# RobotCtrl_Core.net
KiCad netlist of a schematic drawn in Altium Designer
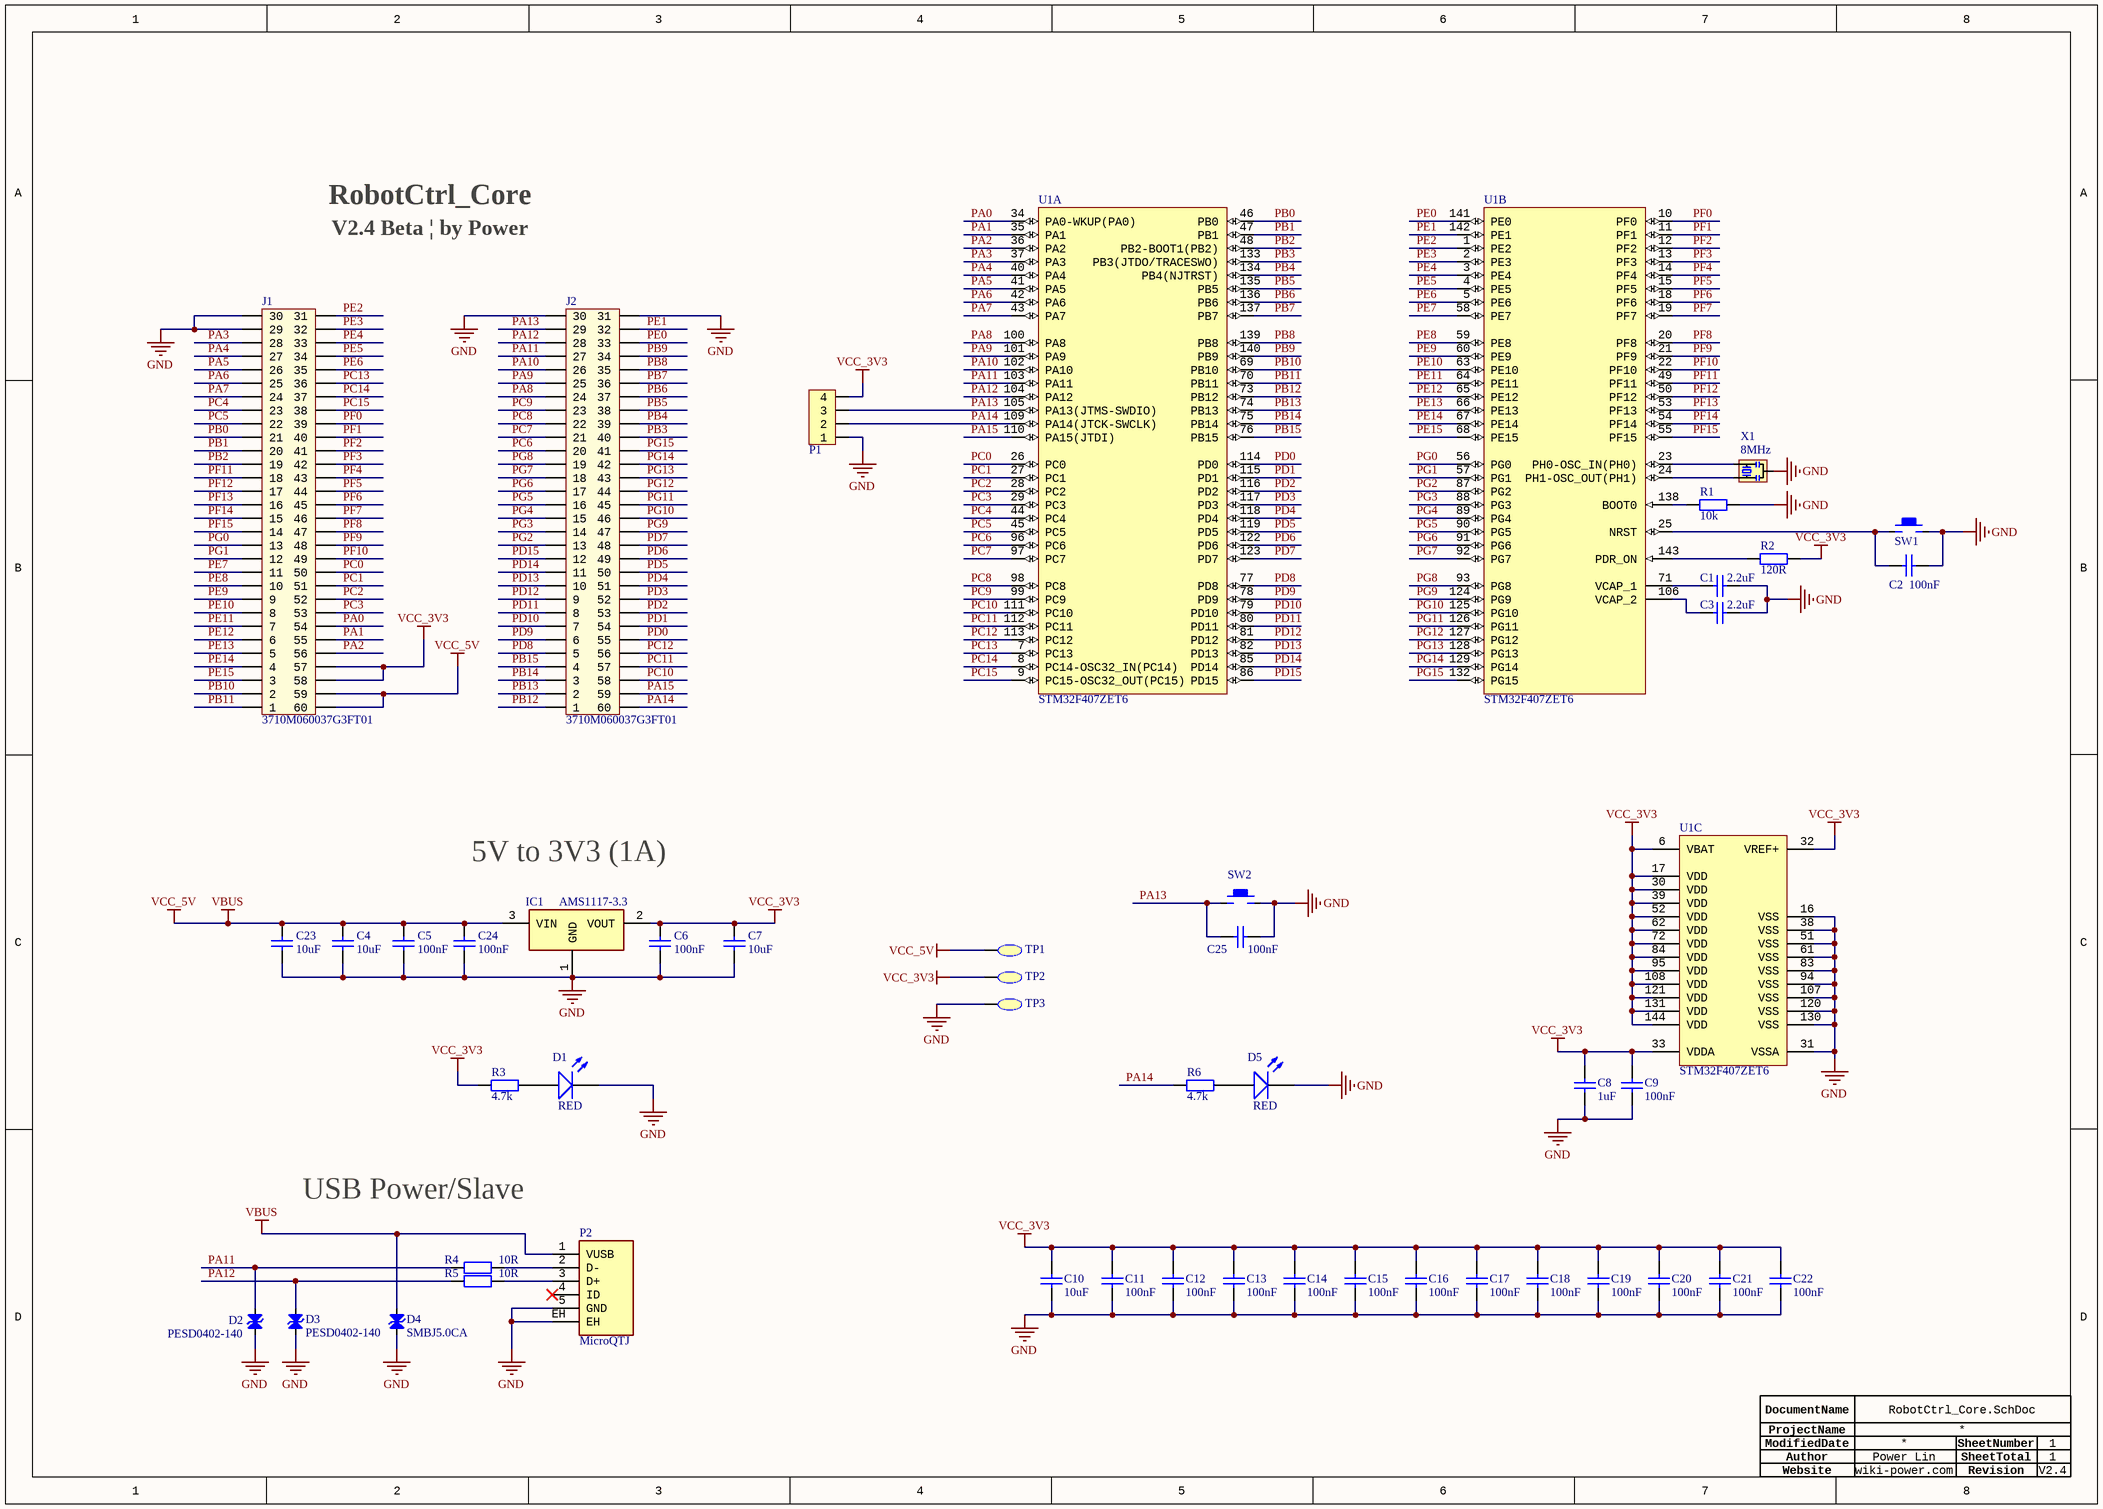
[diagram p0: RobotCtrl_Core.SchDoc]

(export (version "E")
  (design (tool "Eeschema 10.0.6"))
  (components
    (comp (ref "C1")
      (value "2.2uF")
      (footprint "CAP-0603")
      (description "贴片电容")
      (libsource (lib "Power_Lib_Altium") (part "CAP"))
    )
    (comp (ref "C2")
      (value "100nF")
      (footprint "CAP-0603")
      (description "贴片电容")
      (libsource (lib "Power_Lib_Altium") (part "CAP"))
    )
    (comp (ref "C3")
      (value "2.2uF")
      (footprint "CAP-0603")
      (description "贴片电容")
      (libsource (lib "Power_Lib_Altium") (part "CAP"))
    )
    (comp (ref "C4")
      (value "10uF")
      (footprint "CAP-0603")
      (description "贴片电容")
      (libsource (lib "Power_Lib_Altium") (part "CAP"))
    )
    (comp (ref "C5")
      (value "100nF")
      (footprint "CAP-0603")
      (description "贴片电容")
      (libsource (lib "Power_Lib_Altium") (part "CAP"))
    )
    (comp (ref "C6")
      (value "100nF")
      (footprint "CAP-0603")
      (description "贴片电容")
      (libsource (lib "Power_Lib_Altium") (part "CAP"))
    )
    (comp (ref "C7")
      (value "10uF")
      (footprint "CAP-0603")
      (description "贴片电容")
      (libsource (lib "Power_Lib_Altium") (part "CAP"))
    )
    (comp (ref "C8")
      (value "1uF")
      (footprint "CAP-0402")
      (description "贴片电容")
      (libsource (lib "Power_Lib_Altium") (part "CAP"))
    )
    (comp (ref "C9")
      (value "100nF")
      (footprint "CAP-0402")
      (description "贴片电容")
      (libsource (lib "Power_Lib_Altium") (part "CAP"))
    )
    (comp (ref "C10")
      (value "10uF")
      (footprint "CAP-0402")
      (description "贴片电容")
      (libsource (lib "Power_Lib_Altium") (part "CAP"))
    )
    (comp (ref "C11")
      (value "100nF")
      (footprint "CAP-0402")
      (description "贴片电容")
      (libsource (lib "Power_Lib_Altium") (part "CAP"))
    )
    (comp (ref "C12")
      (value "100nF")
      (footprint "CAP-0402")
      (description "贴片电容")
      (libsource (lib "Power_Lib_Altium") (part "CAP"))
    )
    (comp (ref "C13")
      (value "100nF")
      (footprint "CAP-0402")
      (description "贴片电容")
      (libsource (lib "Power_Lib_Altium") (part "CAP"))
    )
    (comp (ref "C14")
      (value "100nF")
      (footprint "CAP-0402")
      (description "贴片电容")
      (libsource (lib "Power_Lib_Altium") (part "CAP"))
    )
    (comp (ref "C15")
      (value "100nF")
      (footprint "CAP-0402")
      (description "贴片电容")
      (libsource (lib "Power_Lib_Altium") (part "CAP"))
    )
    (comp (ref "C16")
      (value "100nF")
      (footprint "CAP-0402")
      (description "贴片电容")
      (libsource (lib "Power_Lib_Altium") (part "CAP"))
    )
    (comp (ref "C17")
      (value "100nF")
      (footprint "CAP-0402")
      (description "贴片电容")
      (libsource (lib "Power_Lib_Altium") (part "CAP"))
    )
    (comp (ref "C18")
      (value "100nF")
      (footprint "CAP-0402")
      (description "贴片电容")
      (libsource (lib "Power_Lib_Altium") (part "CAP"))
    )
    (comp (ref "C19")
      (value "100nF")
      (footprint "CAP-0402")
      (description "贴片电容")
      (libsource (lib "Power_Lib_Altium") (part "CAP"))
    )
    (comp (ref "C20")
      (value "100nF")
      (footprint "CAP-0402")
      (description "贴片电容")
      (libsource (lib "Power_Lib_Altium") (part "CAP"))
    )
    (comp (ref "C21")
      (value "100nF")
      (footprint "CAP-0402")
      (description "贴片电容")
      (libsource (lib "Power_Lib_Altium") (part "CAP"))
    )
    (comp (ref "C22")
      (value "100nF")
      (footprint "CAP-0402")
      (description "贴片电容")
      (libsource (lib "Power_Lib_Altium") (part "CAP"))
    )
    (comp (ref "C23")
      (value "10uF")
      (footprint "CAP-0603")
      (description "贴片电容")
      (libsource (lib "Power_Lib_Altium") (part "CAP"))
    )
    (comp (ref "C24")
      (value "100nF")
      (footprint "CAP-0603")
      (description "贴片电容")
      (libsource (lib "Power_Lib_Altium") (part "CAP"))
    )
    (comp (ref "C25")
      (value "100nF")
      (footprint "CAP-0603")
      (description "贴片电容")
      (libsource (lib "Power_Lib_Altium") (part "CAP"))
    )
    (comp (ref "D1")
      (value "RED")
      (footprint "LED-0603")
      (description "发光二极管")
      (libsource (lib "Power_Lib_Altium") (part "LED"))
    )
    (comp (ref "D2")
      (value "PESD0402-140")
      (footprint "D-0402")
      (libsource (lib "Power_Lib_Altium") (part "TVS_C"))
    )
    (comp (ref "D3")
      (value "PESD0402-140")
      (footprint "D-0402")
      (libsource (lib "Power_Lib_Altium") (part "TVS_C"))
    )
    (comp (ref "D4")
      (value "SMBJ5.0CA")
      (footprint "DO-214AA/SMB")
      (description "Brightking / MDD")
      (libsource (lib "Power_Lib_Altium") (part "TVS_C"))
    )
    (comp (ref "D5")
      (value "RED")
      (footprint "LED-0603")
      (description "发光二极管")
      (libsource (lib "Power_Lib_Altium") (part "LED"))
    )
    (comp (ref "IC1")
      (value "AMS1117-3.3")
      (footprint "SOT-223")
      (description "AMS1117-3.3 1.0A")
      (fields (field (name "MANUFACTURER_PART_NUMBER") "SI2302DS") (field (name "RS PART NUMBER") "7983053P"))
      (libsource (lib "Power_Lib_Altium") (part "AMS1117"))
    )
    (comp (ref "J1")
      (value "3710M060037G3FT01")
      (footprint "3710M060037G3FT01")
      (description "B2B Connector")
      (libsource (lib "Power_Lib_Altium") (part "3710M/F"))
    )
    (comp (ref "J2")
      (value "3710M060037G3FT01")
      (footprint "3710M060037G3FT01")
      (description "B2B Connector")
      (libsource (lib "Power_Lib_Altium") (part "3710M/F"))
    )
    (comp (ref "P1")
      (value "HDR1x4_2.54")
      (footprint "HDR1X4_2.54")
      (description "Header")
      (libsource (lib "Power_Lib_Altium") (part "HDR1x4_2.54"))
    )
    (comp (ref "P2")
      (value "MicroQTJ")
      (footprint "USB-MICRO")
      (description "USB_MICRO")
      (libsource (lib "Power_Lib_Altium") (part "USB_MICRO"))
    )
    (comp (ref "R1")
      (value "10k")
      (footprint "R-0603")
      (description "贴片电阻")
      (libsource (lib "") (part "RES_1"))
    )
    (comp (ref "R2")
      (value "120R")
      (footprint "R-0603")
      (description "贴片电阻")
      (libsource (lib "") (part "RES_1"))
    )
    (comp (ref "R3")
      (value "4.7k")
      (footprint "R-0603")
      (description "贴片电阻")
      (libsource (lib "") (part "RES_1"))
    )
    (comp (ref "R4")
      (value "10R")
      (footprint "R-0603")
      (description "贴片电阻")
      (libsource (lib "Power_Lib_Altium") (part "RES"))
    )
    (comp (ref "R5")
      (value "10R")
      (footprint "R-0603")
      (description "贴片电阻")
      (libsource (lib "Power_Lib_Altium") (part "RES"))
    )
    (comp (ref "R6")
      (value "4.7k")
      (footprint "R-0603")
      (description "贴片电阻")
      (libsource (lib "") (part "RES_1"))
    )
    (comp (ref "SW1")
      (value "KEY")
      (footprint "KEY-4P-4.2*3.4*2.5")
      (description "按键开关")
      (libsource (lib "Power_Lib_Altium") (part "KEY"))
    )
    (comp (ref "SW2")
      (value "KEY")
      (footprint "KEY-4P-4.2*3.4*2.5")
      (description "按键开关")
      (libsource (lib "Power_Lib_Altium") (part "KEY"))
    )
    (comp (ref "TP1")
      (value "TestPoint")
      (footprint "TestPoint")
      (description "测试点")
      (libsource (lib "Power_Lib_Altium") (part "TestPoint"))
    )
    (comp (ref "TP2")
      (value "TestPoint")
      (footprint "TestPoint")
      (description "测试点")
      (libsource (lib "Power_Lib_Altium") (part "TestPoint"))
    )
    (comp (ref "TP3")
      (value "TestPoint")
      (footprint "TestPoint")
      (description "测试点")
      (libsource (lib "Power_Lib_Altium") (part "TestPoint"))
    )
    (comp (ref "U1")
      (value "STM32F407ZET6")
      (footprint "STM-LQFP144_N")
      (fields (field (name "MANUFACTURER") "STMicroelectronics"))
      (libsource (lib "Power_Lib_Altium") (part "STM32F407ZET6"))
    )
    (comp (ref "X1")
      (value "8MHz")
      (footprint "SMD3213-3P")
      (description "CSTCE8M00G15C99-R0")
      (libsource (lib "Power_Lib_Altium") (part "XTAL"))
    )
  )
  (nets
    (net (code "1") (name "/PA0") (class "Default")
      (node (ref "J1") (pin "54") (pinfunction "54_54") (pintype "passive"))
      (node (ref "U1") (pin "34") (pinfunction "PA0-WKUP(PA0)_34") (pintype "bidirectional"))
    )
    (net (code "2") (name "/PA1") (class "Default")
      (node (ref "J1") (pin "55") (pinfunction "55_55") (pintype "passive"))
      (node (ref "U1") (pin "35") (pinfunction "PA1_35") (pintype "bidirectional"))
    )
    (net (code "3") (name "/PA2") (class "Default")
      (node (ref "J1") (pin "56") (pinfunction "56_56") (pintype "passive"))
      (node (ref "U1") (pin "36") (pinfunction "PA2_36") (pintype "bidirectional"))
    )
    (net (code "4") (name "/PA3") (class "Default")
      (node (ref "J1") (pin "28") (pinfunction "28_28") (pintype "passive"))
      (node (ref "U1") (pin "37") (pinfunction "PA3_37") (pintype "bidirectional"))
    )
    (net (code "5") (name "/PA4") (class "Default")
      (node (ref "J1") (pin "27") (pinfunction "27_27") (pintype "passive"))
      (node (ref "U1") (pin "40") (pinfunction "PA4_40") (pintype "bidirectional"))
    )
    (net (code "6") (name "/PA5") (class "Default")
      (node (ref "J1") (pin "26") (pinfunction "26_26") (pintype "passive"))
      (node (ref "U1") (pin "41") (pinfunction "PA5_41") (pintype "bidirectional"))
    )
    (net (code "7") (name "/PA6") (class "Default")
      (node (ref "J1") (pin "25") (pinfunction "25_25") (pintype "passive"))
      (node (ref "U1") (pin "42") (pinfunction "PA6_42") (pintype "bidirectional"))
    )
    (net (code "8") (name "/PA7") (class "Default")
      (node (ref "J1") (pin "24") (pinfunction "24_24") (pintype "passive"))
      (node (ref "U1") (pin "43") (pinfunction "PA7_43") (pintype "bidirectional"))
    )
    (net (code "9") (name "/PA8") (class "Default")
      (node (ref "J2") (pin "24") (pinfunction "24_24") (pintype "passive"))
      (node (ref "U1") (pin "100") (pinfunction "PA8_100") (pintype "bidirectional"))
    )
    (net (code "10") (name "/PA9") (class "Default")
      (node (ref "J2") (pin "25") (pinfunction "25_25") (pintype "passive"))
      (node (ref "U1") (pin "101") (pinfunction "PA9_101") (pintype "bidirectional"))
    )
    (net (code "11") (name "/PA10") (class "Default")
      (node (ref "J2") (pin "26") (pinfunction "26_26") (pintype "passive"))
      (node (ref "U1") (pin "102") (pinfunction "PA10_102") (pintype "bidirectional"))
    )
    (net (code "12") (name "/PA11") (class "Default")
      (node (ref "D2") (pin "2") (pinfunction "2_2") (pintype "passive"))
      (node (ref "J2") (pin "27") (pinfunction "27_27") (pintype "passive"))
      (node (ref "R4") (pin "1") (pinfunction "1_1") (pintype "passive"))
      (node (ref "U1") (pin "103") (pinfunction "PA11_103") (pintype "bidirectional"))
    )
    (net (code "13") (name "/PA12") (class "Default")
      (node (ref "D3") (pin "2") (pinfunction "2_2") (pintype "passive"))
      (node (ref "J2") (pin "28") (pinfunction "28_28") (pintype "passive"))
      (node (ref "R5") (pin "1") (pinfunction "1_1") (pintype "passive"))
      (node (ref "U1") (pin "104") (pinfunction "PA12_104") (pintype "bidirectional"))
    )
    (net (code "14") (name "/PA13") (class "Default")
      (node (ref "C25") (pin "2") (pinfunction "2_2") (pintype "passive"))
      (node (ref "J2") (pin "29") (pinfunction "29_29") (pintype "passive"))
      (node (ref "P1") (pin "3") (pinfunction "3_3") (pintype "passive"))
      (node (ref "SW2") (pin "1") (pinfunction "1_1") (pintype "passive"))
      (node (ref "U1") (pin "105") (pinfunction "PA13(JTMS-SWDIO)_105") (pintype "bidirectional"))
    )
    (net (code "15") (name "/PA14") (class "Default")
      (node (ref "J2") (pin "60") (pinfunction "60_60") (pintype "passive"))
      (node (ref "P1") (pin "2") (pinfunction "2_2") (pintype "passive"))
      (node (ref "R6") (pin "2") (pinfunction "2_2") (pintype "passive"))
      (node (ref "U1") (pin "109") (pinfunction "PA14(JTCK-SWCLK)_109") (pintype "bidirectional"))
    )
    (net (code "16") (name "/PA15") (class "Default")
      (node (ref "J2") (pin "59") (pinfunction "59_59") (pintype "passive"))
      (node (ref "U1") (pin "110") (pinfunction "PA15(JTDI)_110") (pintype "bidirectional"))
    )
    (net (code "17") (name "/PB0") (class "Default")
      (node (ref "J1") (pin "21") (pinfunction "21_21") (pintype "passive"))
      (node (ref "U1") (pin "46") (pinfunction "PB0_46") (pintype "bidirectional"))
    )
    (net (code "18") (name "/PB1") (class "Default")
      (node (ref "J1") (pin "20") (pinfunction "20_20") (pintype "passive"))
      (node (ref "U1") (pin "47") (pinfunction "PB1_47") (pintype "bidirectional"))
    )
    (net (code "19") (name "/PB2") (class "Default")
      (node (ref "J1") (pin "19") (pinfunction "19_19") (pintype "passive"))
      (node (ref "U1") (pin "48") (pinfunction "PB2-BOOT1(PB2)_48") (pintype "bidirectional"))
    )
    (net (code "20") (name "/PB3") (class "Default")
      (node (ref "J2") (pin "40") (pinfunction "40_40") (pintype "passive"))
      (node (ref "U1") (pin "133") (pinfunction "PB3(JTDO/TRACESWO)_133") (pintype "bidirectional"))
    )
    (net (code "21") (name "/PB4") (class "Default")
      (node (ref "J2") (pin "39") (pinfunction "39_39") (pintype "passive"))
      (node (ref "U1") (pin "134") (pinfunction "PB4(NJTRST)_134") (pintype "bidirectional"))
    )
    (net (code "22") (name "/PB5") (class "Default")
      (node (ref "J2") (pin "38") (pinfunction "38_38") (pintype "passive"))
      (node (ref "U1") (pin "135") (pinfunction "PB5_135") (pintype "bidirectional"))
    )
    (net (code "23") (name "/PB6") (class "Default")
      (node (ref "J2") (pin "37") (pinfunction "37_37") (pintype "passive"))
      (node (ref "U1") (pin "136") (pinfunction "PB6_136") (pintype "bidirectional"))
    )
    (net (code "24") (name "/PB7") (class "Default")
      (node (ref "J2") (pin "36") (pinfunction "36_36") (pintype "passive"))
      (node (ref "U1") (pin "137") (pinfunction "PB7_137") (pintype "bidirectional"))
    )
    (net (code "25") (name "/PB8") (class "Default")
      (node (ref "J2") (pin "35") (pinfunction "35_35") (pintype "passive"))
      (node (ref "U1") (pin "139") (pinfunction "PB8_139") (pintype "bidirectional"))
    )
    (net (code "26") (name "/PB9") (class "Default")
      (node (ref "J2") (pin "34") (pinfunction "34_34") (pintype "passive"))
      (node (ref "U1") (pin "140") (pinfunction "PB9_140") (pintype "bidirectional"))
    )
    (net (code "27") (name "/PB10") (class "Default")
      (node (ref "J1") (pin "2") (pinfunction "2_2") (pintype "passive"))
      (node (ref "U1") (pin "69") (pinfunction "PB10_69") (pintype "bidirectional"))
    )
    (net (code "28") (name "/PB11") (class "Default")
      (node (ref "J1") (pin "1") (pinfunction "1_1") (pintype "passive"))
      (node (ref "U1") (pin "70") (pinfunction "PB11_70") (pintype "bidirectional"))
    )
    (net (code "29") (name "/PB12") (class "Default")
      (node (ref "J2") (pin "1") (pinfunction "1_1") (pintype "passive"))
      (node (ref "U1") (pin "73") (pinfunction "PB12_73") (pintype "bidirectional"))
    )
    (net (code "30") (name "/PB13") (class "Default")
      (node (ref "J2") (pin "2") (pinfunction "2_2") (pintype "passive"))
      (node (ref "U1") (pin "74") (pinfunction "PB13_74") (pintype "bidirectional"))
    )
    (net (code "31") (name "/PB14") (class "Default")
      (node (ref "J2") (pin "3") (pinfunction "3_3") (pintype "passive"))
      (node (ref "U1") (pin "75") (pinfunction "PB14_75") (pintype "bidirectional"))
    )
    (net (code "32") (name "/PB15") (class "Default")
      (node (ref "J2") (pin "4") (pinfunction "4_4") (pintype "passive"))
      (node (ref "U1") (pin "76") (pinfunction "PB15_76") (pintype "bidirectional"))
    )
    (net (code "33") (name "/PC0") (class "Default")
      (node (ref "J1") (pin "50") (pinfunction "50_50") (pintype "passive"))
      (node (ref "U1") (pin "26") (pinfunction "PC0_26") (pintype "bidirectional"))
    )
    (net (code "34") (name "/PC1") (class "Default")
      (node (ref "J1") (pin "51") (pinfunction "51_51") (pintype "passive"))
      (node (ref "U1") (pin "27") (pinfunction "PC1_27") (pintype "bidirectional"))
    )
    (net (code "35") (name "/PC2") (class "Default")
      (node (ref "J1") (pin "52") (pinfunction "52_52") (pintype "passive"))
      (node (ref "U1") (pin "28") (pinfunction "PC2_28") (pintype "bidirectional"))
    )
    (net (code "36") (name "/PC3") (class "Default")
      (node (ref "J1") (pin "53") (pinfunction "53_53") (pintype "passive"))
      (node (ref "U1") (pin "29") (pinfunction "PC3_29") (pintype "bidirectional"))
    )
    (net (code "37") (name "/PC4") (class "Default")
      (node (ref "J1") (pin "23") (pinfunction "23_23") (pintype "passive"))
      (node (ref "U1") (pin "44") (pinfunction "PC4_44") (pintype "bidirectional"))
    )
    (net (code "38") (name "/PC5") (class "Default")
      (node (ref "J1") (pin "22") (pinfunction "22_22") (pintype "passive"))
      (node (ref "U1") (pin "45") (pinfunction "PC5_45") (pintype "bidirectional"))
    )
    (net (code "39") (name "/PC6") (class "Default")
      (node (ref "J2") (pin "20") (pinfunction "20_20") (pintype "passive"))
      (node (ref "U1") (pin "96") (pinfunction "PC6_96") (pintype "bidirectional"))
    )
    (net (code "40") (name "/PC7") (class "Default")
      (node (ref "J2") (pin "21") (pinfunction "21_21") (pintype "passive"))
      (node (ref "U1") (pin "97") (pinfunction "PC7_97") (pintype "bidirectional"))
    )
    (net (code "41") (name "/PC8") (class "Default")
      (node (ref "J2") (pin "22") (pinfunction "22_22") (pintype "passive"))
      (node (ref "U1") (pin "98") (pinfunction "PC8_98") (pintype "bidirectional"))
    )
    (net (code "42") (name "/PC9") (class "Default")
      (node (ref "J2") (pin "23") (pinfunction "23_23") (pintype "passive"))
      (node (ref "U1") (pin "99") (pinfunction "PC9_99") (pintype "bidirectional"))
    )
    (net (code "43") (name "/PC10") (class "Default")
      (node (ref "J2") (pin "58") (pinfunction "58_58") (pintype "passive"))
      (node (ref "U1") (pin "111") (pinfunction "PC10_111") (pintype "bidirectional"))
    )
    (net (code "44") (name "/PC11") (class "Default")
      (node (ref "J2") (pin "57") (pinfunction "57_57") (pintype "passive"))
      (node (ref "U1") (pin "112") (pinfunction "PC11_112") (pintype "bidirectional"))
    )
    (net (code "45") (name "/PC12") (class "Default")
      (node (ref "J2") (pin "56") (pinfunction "56_56") (pintype "passive"))
      (node (ref "U1") (pin "113") (pinfunction "PC12_113") (pintype "bidirectional"))
    )
    (net (code "46") (name "/PC13") (class "Default")
      (node (ref "J1") (pin "36") (pinfunction "36_36") (pintype "passive"))
      (node (ref "U1") (pin "7") (pinfunction "PC13_7") (pintype "bidirectional"))
    )
    (net (code "47") (name "/PC14") (class "Default")
      (node (ref "J1") (pin "37") (pinfunction "37_37") (pintype "passive"))
      (node (ref "U1") (pin "8") (pinfunction "PC14-OSC32_IN(PC14)_8") (pintype "bidirectional"))
    )
    (net (code "48") (name "/PC15") (class "Default")
      (node (ref "J1") (pin "38") (pinfunction "38_38") (pintype "passive"))
      (node (ref "U1") (pin "9") (pinfunction "PC15-OSC32_OUT(PC15)_9") (pintype "bidirectional"))
    )
    (net (code "49") (name "/PD0") (class "Default")
      (node (ref "J2") (pin "55") (pinfunction "55_55") (pintype "passive"))
      (node (ref "U1") (pin "114") (pinfunction "PD0_114") (pintype "bidirectional"))
    )
    (net (code "50") (name "/PD1") (class "Default")
      (node (ref "J2") (pin "54") (pinfunction "54_54") (pintype "passive"))
      (node (ref "U1") (pin "115") (pinfunction "PD1_115") (pintype "bidirectional"))
    )
    (net (code "51") (name "/PD2") (class "Default")
      (node (ref "J2") (pin "53") (pinfunction "53_53") (pintype "passive"))
      (node (ref "U1") (pin "116") (pinfunction "PD2_116") (pintype "bidirectional"))
    )
    (net (code "52") (name "/PD3") (class "Default")
      (node (ref "J2") (pin "52") (pinfunction "52_52") (pintype "passive"))
      (node (ref "U1") (pin "117") (pinfunction "PD3_117") (pintype "bidirectional"))
    )
    (net (code "53") (name "/PD4") (class "Default")
      (node (ref "J2") (pin "51") (pinfunction "51_51") (pintype "passive"))
      (node (ref "U1") (pin "118") (pinfunction "PD4_118") (pintype "bidirectional"))
    )
    (net (code "54") (name "/PD5") (class "Default")
      (node (ref "J2") (pin "50") (pinfunction "50_50") (pintype "passive"))
      (node (ref "U1") (pin "119") (pinfunction "PD5_119") (pintype "bidirectional"))
    )
    (net (code "55") (name "/PD6") (class "Default")
      (node (ref "J2") (pin "49") (pinfunction "49_49") (pintype "passive"))
      (node (ref "U1") (pin "122") (pinfunction "PD6_122") (pintype "bidirectional"))
    )
    (net (code "56") (name "/PD7") (class "Default")
      (node (ref "J2") (pin "48") (pinfunction "48_48") (pintype "passive"))
      (node (ref "U1") (pin "123") (pinfunction "PD7_123") (pintype "bidirectional"))
    )
    (net (code "57") (name "/PD8") (class "Default")
      (node (ref "J2") (pin "5") (pinfunction "5_5") (pintype "passive"))
      (node (ref "U1") (pin "77") (pinfunction "PD8_77") (pintype "bidirectional"))
    )
    (net (code "58") (name "/PD9") (class "Default")
      (node (ref "J2") (pin "6") (pinfunction "6_6") (pintype "passive"))
      (node (ref "U1") (pin "78") (pinfunction "PD9_78") (pintype "bidirectional"))
    )
    (net (code "59") (name "/PD10") (class "Default")
      (node (ref "J2") (pin "7") (pinfunction "7_7") (pintype "passive"))
      (node (ref "U1") (pin "79") (pinfunction "PD10_79") (pintype "bidirectional"))
    )
    (net (code "60") (name "/PD11") (class "Default")
      (node (ref "J2") (pin "8") (pinfunction "8_8") (pintype "passive"))
      (node (ref "U1") (pin "80") (pinfunction "PD11_80") (pintype "bidirectional"))
    )
    (net (code "61") (name "/PD12") (class "Default")
      (node (ref "J2") (pin "9") (pinfunction "9_9") (pintype "passive"))
      (node (ref "U1") (pin "81") (pinfunction "PD12_81") (pintype "bidirectional"))
    )
    (net (code "62") (name "/PD13") (class "Default")
      (node (ref "J2") (pin "10") (pinfunction "10_10") (pintype "passive"))
      (node (ref "U1") (pin "82") (pinfunction "PD13_82") (pintype "bidirectional"))
    )
    (net (code "63") (name "/PD14") (class "Default")
      (node (ref "J2") (pin "11") (pinfunction "11_11") (pintype "passive"))
      (node (ref "U1") (pin "85") (pinfunction "PD14_85") (pintype "bidirectional"))
    )
    (net (code "64") (name "/PD15") (class "Default")
      (node (ref "J2") (pin "12") (pinfunction "12_12") (pintype "passive"))
      (node (ref "U1") (pin "86") (pinfunction "PD15_86") (pintype "bidirectional"))
    )
    (net (code "65") (name "/PE0") (class "Default")
      (node (ref "J2") (pin "33") (pinfunction "33_33") (pintype "passive"))
      (node (ref "U1") (pin "141") (pinfunction "PE0_141") (pintype "bidirectional"))
    )
    (net (code "66") (name "/PE1") (class "Default")
      (node (ref "J2") (pin "32") (pinfunction "32_32") (pintype "passive"))
      (node (ref "U1") (pin "142") (pinfunction "PE1_142") (pintype "bidirectional"))
    )
    (net (code "67") (name "/PE2") (class "Default")
      (node (ref "J1") (pin "31") (pinfunction "31_31") (pintype "passive"))
      (node (ref "U1") (pin "1") (pinfunction "PE2_1") (pintype "bidirectional"))
    )
    (net (code "68") (name "/PE3") (class "Default")
      (node (ref "J1") (pin "32") (pinfunction "32_32") (pintype "passive"))
      (node (ref "U1") (pin "2") (pinfunction "PE3_2") (pintype "bidirectional"))
    )
    (net (code "69") (name "/PE4") (class "Default")
      (node (ref "J1") (pin "33") (pinfunction "33_33") (pintype "passive"))
      (node (ref "U1") (pin "3") (pinfunction "PE4_3") (pintype "bidirectional"))
    )
    (net (code "70") (name "/PE5") (class "Default")
      (node (ref "J1") (pin "34") (pinfunction "34_34") (pintype "passive"))
      (node (ref "U1") (pin "4") (pinfunction "PE5_4") (pintype "bidirectional"))
    )
    (net (code "71") (name "/PE6") (class "Default")
      (node (ref "J1") (pin "35") (pinfunction "35_35") (pintype "passive"))
      (node (ref "U1") (pin "5") (pinfunction "PE6_5") (pintype "bidirectional"))
    )
    (net (code "72") (name "/PE7") (class "Default")
      (node (ref "J1") (pin "11") (pinfunction "11_11") (pintype "passive"))
      (node (ref "U1") (pin "58") (pinfunction "PE7_58") (pintype "bidirectional"))
    )
    (net (code "73") (name "/PE8") (class "Default")
      (node (ref "J1") (pin "10") (pinfunction "10_10") (pintype "passive"))
      (node (ref "U1") (pin "59") (pinfunction "PE8_59") (pintype "bidirectional"))
    )
    (net (code "74") (name "/PE9") (class "Default")
      (node (ref "J1") (pin "9") (pinfunction "9_9") (pintype "passive"))
      (node (ref "U1") (pin "60") (pinfunction "PE9_60") (pintype "bidirectional"))
    )
    (net (code "75") (name "/PE10") (class "Default")
      (node (ref "J1") (pin "8") (pinfunction "8_8") (pintype "passive"))
      (node (ref "U1") (pin "63") (pinfunction "PE10_63") (pintype "bidirectional"))
    )
    (net (code "76") (name "/PE11") (class "Default")
      (node (ref "J1") (pin "7") (pinfunction "7_7") (pintype "passive"))
      (node (ref "U1") (pin "64") (pinfunction "PE11_64") (pintype "bidirectional"))
    )
    (net (code "77") (name "/PE12") (class "Default")
      (node (ref "J1") (pin "6") (pinfunction "6_6") (pintype "passive"))
      (node (ref "U1") (pin "65") (pinfunction "PE12_65") (pintype "bidirectional"))
    )
    (net (code "78") (name "/PE13") (class "Default")
      (node (ref "J1") (pin "5") (pinfunction "5_5") (pintype "passive"))
      (node (ref "U1") (pin "66") (pinfunction "PE13_66") (pintype "bidirectional"))
    )
    (net (code "79") (name "/PE14") (class "Default")
      (node (ref "J1") (pin "4") (pinfunction "4_4") (pintype "passive"))
      (node (ref "U1") (pin "67") (pinfunction "PE14_67") (pintype "bidirectional"))
    )
    (net (code "80") (name "/PE15") (class "Default")
      (node (ref "J1") (pin "3") (pinfunction "3_3") (pintype "passive"))
      (node (ref "U1") (pin "68") (pinfunction "PE15_68") (pintype "bidirectional"))
    )
    (net (code "81") (name "/PF0") (class "Default")
      (node (ref "J1") (pin "39") (pinfunction "39_39") (pintype "passive"))
      (node (ref "U1") (pin "10") (pinfunction "PF0_10") (pintype "bidirectional"))
    )
    (net (code "82") (name "/PF1") (class "Default")
      (node (ref "J1") (pin "40") (pinfunction "40_40") (pintype "passive"))
      (node (ref "U1") (pin "11") (pinfunction "PF1_11") (pintype "bidirectional"))
    )
    (net (code "83") (name "/PF2") (class "Default")
      (node (ref "J1") (pin "41") (pinfunction "41_41") (pintype "passive"))
      (node (ref "U1") (pin "12") (pinfunction "PF2_12") (pintype "bidirectional"))
    )
    (net (code "84") (name "/PF3") (class "Default")
      (node (ref "J1") (pin "42") (pinfunction "42_42") (pintype "passive"))
      (node (ref "U1") (pin "13") (pinfunction "PF3_13") (pintype "bidirectional"))
    )
    (net (code "85") (name "/PF4") (class "Default")
      (node (ref "J1") (pin "43") (pinfunction "43_43") (pintype "passive"))
      (node (ref "U1") (pin "14") (pinfunction "PF4_14") (pintype "bidirectional"))
    )
    (net (code "86") (name "/PF5") (class "Default")
      (node (ref "J1") (pin "44") (pinfunction "44_44") (pintype "passive"))
      (node (ref "U1") (pin "15") (pinfunction "PF5_15") (pintype "bidirectional"))
    )
    (net (code "87") (name "/PF6") (class "Default")
      (node (ref "J1") (pin "45") (pinfunction "45_45") (pintype "passive"))
      (node (ref "U1") (pin "18") (pinfunction "PF6_18") (pintype "bidirectional"))
    )
    (net (code "88") (name "/PF7") (class "Default")
      (node (ref "J1") (pin "46") (pinfunction "46_46") (pintype "passive"))
      (node (ref "U1") (pin "19") (pinfunction "PF7_19") (pintype "bidirectional"))
    )
    (net (code "89") (name "/PF8") (class "Default")
      (node (ref "J1") (pin "47") (pinfunction "47_47") (pintype "passive"))
      (node (ref "U1") (pin "20") (pinfunction "PF8_20") (pintype "bidirectional"))
    )
    (net (code "90") (name "/PF9") (class "Default")
      (node (ref "J1") (pin "48") (pinfunction "48_48") (pintype "passive"))
      (node (ref "U1") (pin "21") (pinfunction "PF9_21") (pintype "bidirectional"))
    )
    (net (code "91") (name "/PF10") (class "Default")
      (node (ref "J1") (pin "49") (pinfunction "49_49") (pintype "passive"))
      (node (ref "U1") (pin "22") (pinfunction "PF10_22") (pintype "bidirectional"))
    )
    (net (code "92") (name "/PF11") (class "Default")
      (node (ref "J1") (pin "18") (pinfunction "18_18") (pintype "passive"))
      (node (ref "U1") (pin "49") (pinfunction "PF11_49") (pintype "bidirectional"))
    )
    (net (code "93") (name "/PF12") (class "Default")
      (node (ref "J1") (pin "17") (pinfunction "17_17") (pintype "passive"))
      (node (ref "U1") (pin "50") (pinfunction "PF12_50") (pintype "bidirectional"))
    )
    (net (code "94") (name "/PF13") (class "Default")
      (node (ref "J1") (pin "16") (pinfunction "16_16") (pintype "passive"))
      (node (ref "U1") (pin "53") (pinfunction "PF13_53") (pintype "bidirectional"))
    )
    (net (code "95") (name "/PF14") (class "Default")
      (node (ref "J1") (pin "15") (pinfunction "15_15") (pintype "passive"))
      (node (ref "U1") (pin "54") (pinfunction "PF14_54") (pintype "bidirectional"))
    )
    (net (code "96") (name "/PF15") (class "Default")
      (node (ref "J1") (pin "14") (pinfunction "14_14") (pintype "passive"))
      (node (ref "U1") (pin "55") (pinfunction "PF15_55") (pintype "bidirectional"))
    )
    (net (code "97") (name "/PG0") (class "Default")
      (node (ref "J1") (pin "13") (pinfunction "13_13") (pintype "passive"))
      (node (ref "U1") (pin "56") (pinfunction "PG0_56") (pintype "bidirectional"))
    )
    (net (code "98") (name "/PG1") (class "Default")
      (node (ref "J1") (pin "12") (pinfunction "12_12") (pintype "passive"))
      (node (ref "U1") (pin "57") (pinfunction "PG1_57") (pintype "bidirectional"))
    )
    (net (code "99") (name "/PG2") (class "Default")
      (node (ref "J2") (pin "13") (pinfunction "13_13") (pintype "passive"))
      (node (ref "U1") (pin "87") (pinfunction "PG2_87") (pintype "bidirectional"))
    )
    (net (code "100") (name "/PG3") (class "Default")
      (node (ref "J2") (pin "14") (pinfunction "14_14") (pintype "passive"))
      (node (ref "U1") (pin "88") (pinfunction "PG3_88") (pintype "bidirectional"))
    )
    (net (code "101") (name "/PG4") (class "Default")
      (node (ref "J2") (pin "15") (pinfunction "15_15") (pintype "passive"))
      (node (ref "U1") (pin "89") (pinfunction "PG4_89") (pintype "bidirectional"))
    )
    (net (code "102") (name "/PG5") (class "Default")
      (node (ref "J2") (pin "16") (pinfunction "16_16") (pintype "passive"))
      (node (ref "U1") (pin "90") (pinfunction "PG5_90") (pintype "bidirectional"))
    )
    (net (code "103") (name "/PG6") (class "Default")
      (node (ref "J2") (pin "17") (pinfunction "17_17") (pintype "passive"))
      (node (ref "U1") (pin "91") (pinfunction "PG6_91") (pintype "bidirectional"))
    )
    (net (code "104") (name "/PG7") (class "Default")
      (node (ref "J2") (pin "18") (pinfunction "18_18") (pintype "passive"))
      (node (ref "U1") (pin "92") (pinfunction "PG7_92") (pintype "bidirectional"))
    )
    (net (code "105") (name "/PG8") (class "Default")
      (node (ref "J2") (pin "19") (pinfunction "19_19") (pintype "passive"))
      (node (ref "U1") (pin "93") (pinfunction "PG8_93") (pintype "bidirectional"))
    )
    (net (code "106") (name "/PG9") (class "Default")
      (node (ref "J2") (pin "47") (pinfunction "47_47") (pintype "passive"))
      (node (ref "U1") (pin "124") (pinfunction "PG9_124") (pintype "bidirectional"))
    )
    (net (code "107") (name "/PG10") (class "Default")
      (node (ref "J2") (pin "46") (pinfunction "46_46") (pintype "passive"))
      (node (ref "U1") (pin "125") (pinfunction "PG10_125") (pintype "bidirectional"))
    )
    (net (code "108") (name "/PG11") (class "Default")
      (node (ref "J2") (pin "45") (pinfunction "45_45") (pintype "passive"))
      (node (ref "U1") (pin "126") (pinfunction "PG11_126") (pintype "bidirectional"))
    )
    (net (code "109") (name "/PG12") (class "Default")
      (node (ref "J2") (pin "44") (pinfunction "44_44") (pintype "passive"))
      (node (ref "U1") (pin "127") (pinfunction "PG12_127") (pintype "bidirectional"))
    )
    (net (code "110") (name "/PG13") (class "Default")
      (node (ref "J2") (pin "43") (pinfunction "43_43") (pintype "passive"))
      (node (ref "U1") (pin "128") (pinfunction "PG13_128") (pintype "bidirectional"))
    )
    (net (code "111") (name "/PG14") (class "Default")
      (node (ref "J2") (pin "42") (pinfunction "42_42") (pintype "passive"))
      (node (ref "U1") (pin "129") (pinfunction "PG14_129") (pintype "bidirectional"))
    )
    (net (code "112") (name "/PG15") (class "Default")
      (node (ref "J2") (pin "41") (pinfunction "41_41") (pintype "passive"))
      (node (ref "U1") (pin "132") (pinfunction "PG15_132") (pintype "bidirectional"))
    )
    (net (code "113") (name "GND") (class "Default")
      (node (ref "C1") (pin "2") (pinfunction "2_2") (pintype "passive"))
      (node (ref "C10") (pin "1") (pinfunction "1_1") (pintype "passive"))
      (node (ref "C11") (pin "1") (pinfunction "1_1") (pintype "passive"))
      (node (ref "C12") (pin "1") (pinfunction "1_1") (pintype "passive"))
      (node (ref "C13") (pin "1") (pinfunction "1_1") (pintype "passive"))
      (node (ref "C14") (pin "1") (pinfunction "1_1") (pintype "passive"))
      (node (ref "C15") (pin "1") (pinfunction "1_1") (pintype "passive"))
      (node (ref "C16") (pin "1") (pinfunction "1_1") (pintype "passive"))
      (node (ref "C17") (pin "1") (pinfunction "1_1") (pintype "passive"))
      (node (ref "C18") (pin "1") (pinfunction "1_1") (pintype "passive"))
      (node (ref "C19") (pin "1") (pinfunction "1_1") (pintype "passive"))
      (node (ref "C2") (pin "1") (pinfunction "1_1") (pintype "passive"))
      (node (ref "C20") (pin "1") (pinfunction "1_1") (pintype "passive"))
      (node (ref "C21") (pin "1") (pinfunction "1_1") (pintype "passive"))
      (node (ref "C22") (pin "1") (pinfunction "1_1") (pintype "passive"))
      (node (ref "C23") (pin "1") (pinfunction "1_1") (pintype "passive"))
      (node (ref "C24") (pin "1") (pinfunction "1_1") (pintype "passive"))
      (node (ref "C25") (pin "1") (pinfunction "1_1") (pintype "passive"))
      (node (ref "C3") (pin "2") (pinfunction "2_2") (pintype "passive"))
      (node (ref "C4") (pin "1") (pinfunction "1_1") (pintype "passive"))
      (node (ref "C5") (pin "1") (pinfunction "1_1") (pintype "passive"))
      (node (ref "C6") (pin "1") (pinfunction "1_1") (pintype "passive"))
      (node (ref "C7") (pin "1") (pinfunction "1_1") (pintype "passive"))
      (node (ref "C8") (pin "1") (pinfunction "1_1") (pintype "passive"))
      (node (ref "C9") (pin "1") (pinfunction "1_1") (pintype "passive"))
      (node (ref "D1") (pin "K") (pinfunction "K_K") (pintype "passive"))
      (node (ref "D2") (pin "1") (pinfunction "1_1") (pintype "passive"))
      (node (ref "D3") (pin "1") (pinfunction "1_1") (pintype "passive"))
      (node (ref "D4") (pin "1") (pinfunction "1_1") (pintype "passive"))
      (node (ref "D5") (pin "K") (pinfunction "K_K") (pintype "passive"))
      (node (ref "IC1") (pin "1") (pinfunction "GND_1") (pintype "passive"))
      (node (ref "J1") (pin "29") (pinfunction "29_29") (pintype "passive"))
      (node (ref "J1") (pin "30") (pinfunction "30_30") (pintype "passive"))
      (node (ref "J2") (pin "30") (pinfunction "30_30") (pintype "passive"))
      (node (ref "J2") (pin "31") (pinfunction "31_31") (pintype "passive"))
      (node (ref "P1") (pin "1") (pinfunction "1_1") (pintype "passive"))
      (node (ref "P2") (pin "5") (pinfunction "GND_5") (pintype "passive"))
      (node (ref "P2") (pin "EH") (pinfunction "EH_EH") (pintype "passive"))
      (node (ref "R1") (pin "1") (pinfunction "1_1") (pintype "passive"))
      (node (ref "SW1") (pin "2") (pinfunction "2_2") (pintype "passive"))
      (node (ref "SW2") (pin "2") (pinfunction "2_2") (pintype "passive"))
      (node (ref "TP3") (pin "1") (pinfunction "1_1") (pintype "passive"))
      (node (ref "U1") (pin "107") (pinfunction "VSS_107") (pintype "power_in"))
      (node (ref "U1") (pin "120") (pinfunction "VSS_120") (pintype "power_in"))
      (node (ref "U1") (pin "130") (pinfunction "VSS_130") (pintype "power_in"))
      (node (ref "U1") (pin "16") (pinfunction "VSS_16") (pintype "power_in"))
      (node (ref "U1") (pin "31") (pinfunction "VSSA_31") (pintype "power_in"))
      (node (ref "U1") (pin "38") (pinfunction "VSS_38") (pintype "power_in"))
      (node (ref "U1") (pin "51") (pinfunction "VSS_51") (pintype "power_in"))
      (node (ref "U1") (pin "61") (pinfunction "VSS_61") (pintype "power_in"))
      (node (ref "U1") (pin "83") (pinfunction "VSS_83") (pintype "power_in"))
      (node (ref "U1") (pin "94") (pinfunction "VSS_94") (pintype "power_in"))
      (node (ref "X1") (pin "2") (pinfunction "GND_2") (pintype "passive"))
    )
    (net (code "114") (name "Net-(D1-PadA)") (class "Default")
      (node (ref "D1") (pin "A") (pinfunction "A_A") (pintype "passive"))
      (node (ref "R3") (pin "1") (pinfunction "1_1") (pintype "passive"))
    )
    (net (code "115") (name "Net-(D5-PadA)") (class "Default")
      (node (ref "D5") (pin "A") (pinfunction "A_A") (pintype "passive"))
      (node (ref "R6") (pin "1") (pinfunction "1_1") (pintype "passive"))
    )
    (net (code "116") (name "Net-(P2-D+)") (class "Default")
      (node (ref "P2") (pin "3") (pinfunction "D+_3") (pintype "passive"))
      (node (ref "R5") (pin "2") (pinfunction "2_2") (pintype "passive"))
    )
    (net (code "117") (name "Net-(P2-D-)") (class "Default")
      (node (ref "P2") (pin "2") (pinfunction "D-_2") (pintype "passive"))
      (node (ref "R4") (pin "2") (pinfunction "2_2") (pintype "passive"))
    )
    (net (code "118") (name "Net-(U1B-BOOT0)") (class "Default")
      (node (ref "R1") (pin "2") (pinfunction "2_2") (pintype "passive"))
      (node (ref "U1") (pin "138") (pinfunction "BOOT0_138") (pintype "input"))
    )
    (net (code "119") (name "Net-(U1B-NRST)") (class "Default")
      (node (ref "C2") (pin "2") (pinfunction "2_2") (pintype "passive"))
      (node (ref "SW1") (pin "1") (pinfunction "1_1") (pintype "passive"))
      (node (ref "U1") (pin "25") (pinfunction "NRST_25") (pintype "bidirectional"))
    )
    (net (code "120") (name "Net-(U1B-PDR_ON)") (class "Default")
      (node (ref "R2") (pin "2") (pinfunction "2_2") (pintype "passive"))
      (node (ref "U1") (pin "143") (pinfunction "PDR_ON_143") (pintype "input"))
    )
    (net (code "121") (name "Net-(U1B-PH0-OSC_IN(PH0))") (class "Default")
      (node (ref "U1") (pin "23") (pinfunction "PH0-OSC_IN(PH0)_23") (pintype "bidirectional"))
      (node (ref "X1") (pin "3") (pinfunction "OSC2_3") (pintype "passive"))
    )
    (net (code "122") (name "Net-(U1B-PH1-OSC_OUT(PH1))") (class "Default")
      (node (ref "U1") (pin "24") (pinfunction "PH1-OSC_OUT(PH1)_24") (pintype "bidirectional"))
      (node (ref "X1") (pin "1") (pinfunction "OSC1_1") (pintype "passive"))
    )
    (net (code "123") (name "Net-(U1B-VCAP_1)") (class "Default")
      (node (ref "C1") (pin "1") (pinfunction "1_1") (pintype "passive"))
      (node (ref "U1") (pin "71") (pinfunction "VCAP_1_71") (pintype "power_in"))
    )
    (net (code "124") (name "Net-(U1B-VCAP_2)") (class "Default")
      (node (ref "C3") (pin "1") (pinfunction "1_1") (pintype "passive"))
      (node (ref "U1") (pin "106") (pinfunction "VCAP_2_106") (pintype "power_in"))
    )
    (net (code "125") (name "VBUS") (class "Default")
      (node (ref "C23") (pin "2") (pinfunction "2_2") (pintype "passive"))
      (node (ref "C24") (pin "2") (pinfunction "2_2") (pintype "passive"))
      (node (ref "C4") (pin "2") (pinfunction "2_2") (pintype "passive"))
      (node (ref "C5") (pin "2") (pinfunction "2_2") (pintype "passive"))
      (node (ref "D4") (pin "2") (pinfunction "2_2") (pintype "passive"))
      (node (ref "IC1") (pin "3") (pinfunction "VIN_3") (pintype "passive"))
      (node (ref "J1") (pin "59") (pinfunction "59_59") (pintype "passive"))
      (node (ref "J1") (pin "60") (pinfunction "60_60") (pintype "passive"))
      (node (ref "P2") (pin "1") (pinfunction "VUSB_1") (pintype "passive"))
      (node (ref "TP1") (pin "1") (pinfunction "1_1") (pintype "passive"))
    )
    (net (code "126") (name "VCC_3V3") (class "Default")
      (node (ref "C10") (pin "2") (pinfunction "2_2") (pintype "passive"))
      (node (ref "C11") (pin "2") (pinfunction "2_2") (pintype "passive"))
      (node (ref "C12") (pin "2") (pinfunction "2_2") (pintype "passive"))
      (node (ref "C13") (pin "2") (pinfunction "2_2") (pintype "passive"))
      (node (ref "C14") (pin "2") (pinfunction "2_2") (pintype "passive"))
      (node (ref "C15") (pin "2") (pinfunction "2_2") (pintype "passive"))
      (node (ref "C16") (pin "2") (pinfunction "2_2") (pintype "passive"))
      (node (ref "C17") (pin "2") (pinfunction "2_2") (pintype "passive"))
      (node (ref "C18") (pin "2") (pinfunction "2_2") (pintype "passive"))
      (node (ref "C19") (pin "2") (pinfunction "2_2") (pintype "passive"))
      (node (ref "C20") (pin "2") (pinfunction "2_2") (pintype "passive"))
      (node (ref "C21") (pin "2") (pinfunction "2_2") (pintype "passive"))
      (node (ref "C22") (pin "2") (pinfunction "2_2") (pintype "passive"))
      (node (ref "C6") (pin "2") (pinfunction "2_2") (pintype "passive"))
      (node (ref "C7") (pin "2") (pinfunction "2_2") (pintype "passive"))
      (node (ref "C8") (pin "2") (pinfunction "2_2") (pintype "passive"))
      (node (ref "C9") (pin "2") (pinfunction "2_2") (pintype "passive"))
      (node (ref "IC1") (pin "2") (pinfunction "VOUT_2") (pintype "passive"))
      (node (ref "J1") (pin "57") (pinfunction "57_57") (pintype "passive"))
      (node (ref "J1") (pin "58") (pinfunction "58_58") (pintype "passive"))
      (node (ref "P1") (pin "4") (pinfunction "4_4") (pintype "passive"))
      (node (ref "R2") (pin "1") (pinfunction "1_1") (pintype "passive"))
      (node (ref "R3") (pin "2") (pinfunction "2_2") (pintype "passive"))
      (node (ref "TP2") (pin "1") (pinfunction "1_1") (pintype "passive"))
      (node (ref "U1") (pin "108") (pinfunction "VDD_108") (pintype "power_in"))
      (node (ref "U1") (pin "121") (pinfunction "VDD_121") (pintype "power_in"))
      (node (ref "U1") (pin "131") (pinfunction "VDD_131") (pintype "power_in"))
      (node (ref "U1") (pin "144") (pinfunction "VDD_144") (pintype "power_in"))
      (node (ref "U1") (pin "17") (pinfunction "VDD_17") (pintype "power_in"))
      (node (ref "U1") (pin "30") (pinfunction "VDD_30") (pintype "power_in"))
      (node (ref "U1") (pin "32") (pinfunction "VREF+_32") (pintype "power_in"))
      (node (ref "U1") (pin "33") (pinfunction "VDDA_33") (pintype "power_in"))
      (node (ref "U1") (pin "39") (pinfunction "VDD_39") (pintype "power_in"))
      (node (ref "U1") (pin "52") (pinfunction "VDD_52") (pintype "power_in"))
      (node (ref "U1") (pin "6") (pinfunction "VBAT_6") (pintype "power_in"))
      (node (ref "U1") (pin "62") (pinfunction "VDD_62") (pintype "power_in"))
      (node (ref "U1") (pin "72") (pinfunction "VDD_72") (pintype "power_in"))
      (node (ref "U1") (pin "84") (pinfunction "VDD_84") (pintype "power_in"))
      (node (ref "U1") (pin "95") (pinfunction "VDD_95") (pintype "power_in"))
    )
    (net (code "127") (name "unconnected-(P2-ID-Pad4)") (class "Default")
      (node (ref "P2") (pin "4") (pinfunction "ID_4") (pintype "passive+no_connect"))
    )
  )
)
